# 1bttn-1poti.net
KiCad netlist of a schematic drawn in EAGLE
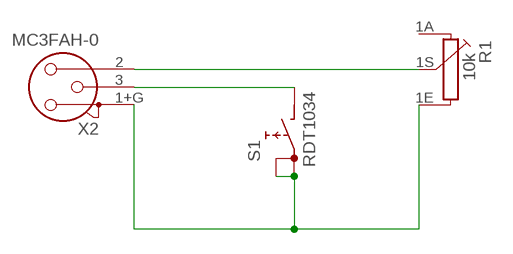
[diagram p0: schematic, sheet 1]

(export (version "E")
  (design (tool "Eeschema 10.0.6"))
  (components
    (comp (ref "R1")
      (value "10k")
      (footprint "eagle-import:PC16-SHM2")
      (libsource (lib "eagle-import") (part "PC16-SHM2"))
    )
    (comp (ref "S1")
      (value "RDT1034")
      (footprint "eagle-import:RDT1034")
      (libsource (lib "eagle-import") (part "RDT1034"))
    )
    (comp (ref "X2")
      (value "MC3FAH-0")
      (footprint "eagle-import:NC3FAH1-0")
      (libsource (lib "eagle-import") (part "MC3?FAH-0"))
    )
  )
  (nets
    (net (code "1") (name "Net-(R1-Pad1S)") (class "Default")
      (node (ref "R1") (pin "1S") (pinfunction "1S_1S") (pintype "passive"))
      (node (ref "X2") (pin "2") (pinfunction "2_2") (pintype "passive"))
    )
    (net (code "2") (name "Net-(S1-PadB)") (class "Default")
      (node (ref "S1") (pin "B") (pinfunction "B_B") (pintype "passive"))
      (node (ref "X2") (pin "3") (pinfunction "3_3") (pintype "passive"))
    )
    (net (code "3") (name "Net-(X2-1)") (class "Default")
      (node (ref "R1") (pin "1E") (pinfunction "1E_1E") (pintype "passive"))
      (node (ref "S1") (pin "A") (pinfunction "A_A") (pintype "passive"))
      (node (ref "S1") (pin "A1") (pinfunction "A1_A1") (pintype "passive"))
      (node (ref "X2") (pin "1+G") (pinfunction "1_1+G") (pintype "passive"))
    )
    (net (code "4") (name "unconnected-(R1-Pad1A)") (class "Default")
      (node (ref "R1") (pin "1A") (pinfunction "1A_1A") (pintype "passive"))
    )
  )
)
